# DMX_module.net
KiCad netlist of a schematic drawn in EAGLE
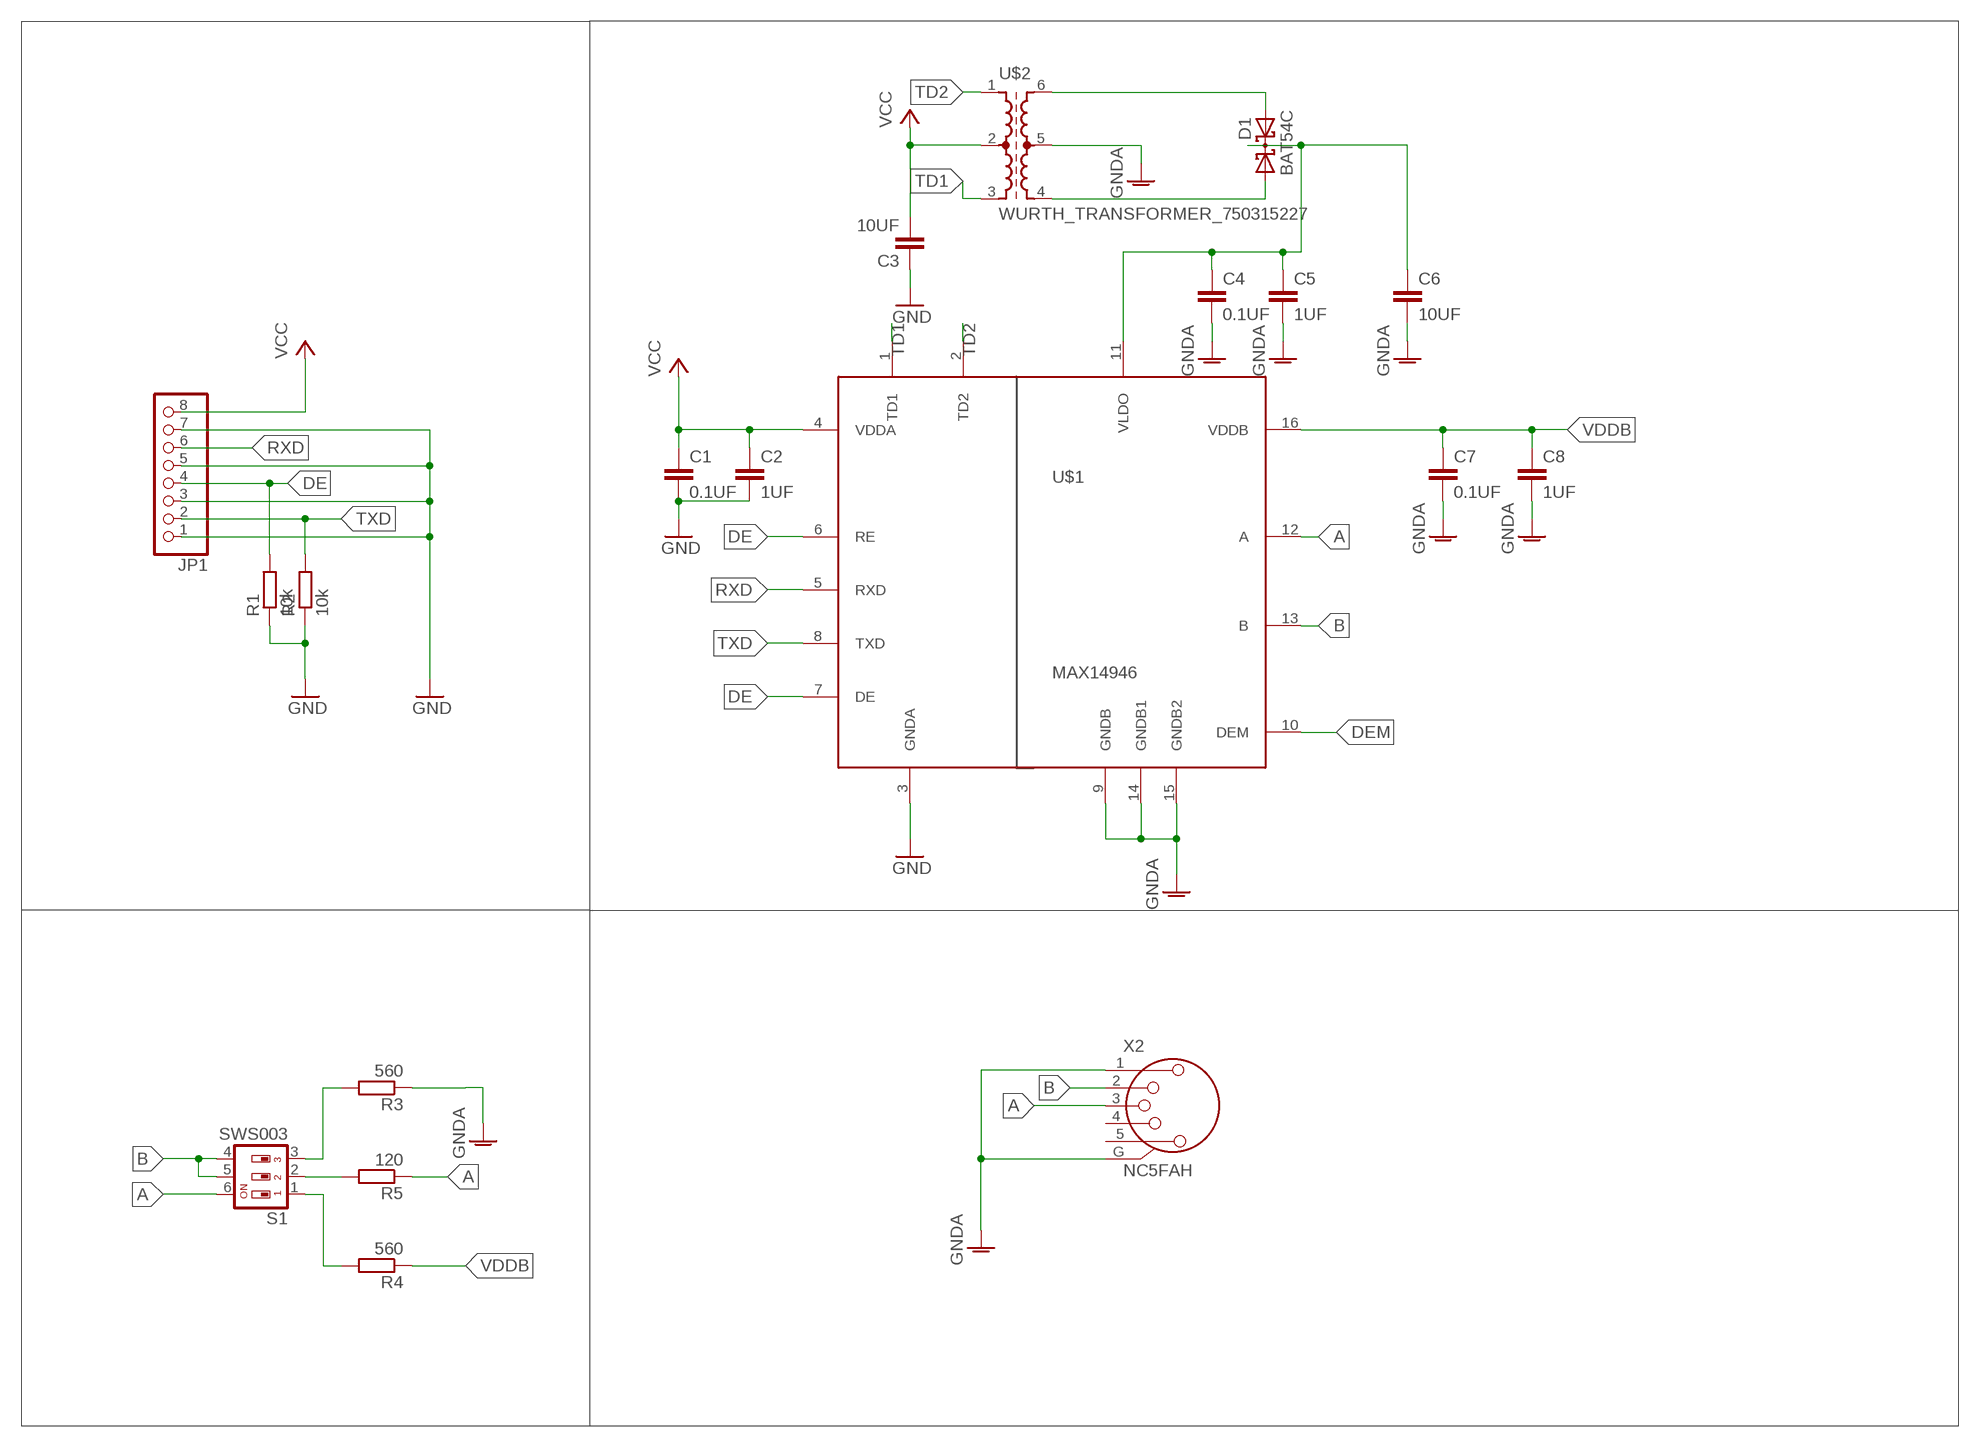
[diagram p0: schematic, sheet 1]

(export (version "E")
  (design (tool "Eeschema 10.0.6"))
  (components
    (comp (ref "C1")
      (value "0.1UF")
      (footprint "eagle-import:C0603")
      (fields (field (name "MF") "AVX") (field (name "MPN") "06033C104KAT2A"))
      (libsource (lib "eagle-import") (part "C-EUC0603"))
    )
    (comp (ref "C2")
      (value "1UF")
      (footprint "eagle-import:C0603")
      (fields (field (name "MF") "AVX") (field (name "MPN") "0603YC105KAT4A"))
      (libsource (lib "eagle-import") (part "C-EUC0603"))
    )
    (comp (ref "C3")
      (value "10UF")
      (footprint "eagle-import:C0805")
      (fields (field (name "MF") "AVX") (field (name "MPN") "08056G106ZAT2A"))
      (libsource (lib "eagle-import") (part "C-EUC0805"))
    )
    (comp (ref "C4")
      (value "0.1UF")
      (footprint "eagle-import:C0603")
      (fields (field (name "MF") "AVX") (field (name "MPN") "06033C104KAT2A"))
      (libsource (lib "eagle-import") (part "C-EUC0603"))
    )
    (comp (ref "C5")
      (value "1UF")
      (footprint "eagle-import:C0603")
      (fields (field (name "MF") "AVX") (field (name "MPN") "0603YC105KAT4A"))
      (libsource (lib "eagle-import") (part "C-EUC0603"))
    )
    (comp (ref "C6")
      (value "10UF")
      (footprint "eagle-import:C0805")
      (fields (field (name "MF") "AVX") (field (name "MPN") "08056G106ZAT2A"))
      (libsource (lib "eagle-import") (part "C-EUC0805"))
    )
    (comp (ref "C7")
      (value "0.1UF")
      (footprint "eagle-import:C0603")
      (fields (field (name "MF") "AVX") (field (name "MPN") "06033C104KAT2A"))
      (libsource (lib "eagle-import") (part "C-EUC0603"))
    )
    (comp (ref "C8")
      (value "1UF")
      (footprint "eagle-import:C0603")
      (fields (field (name "MF") "AVX") (field (name "MPN") "0603YC105KAT4A"))
      (libsource (lib "eagle-import") (part "C-EUC0603"))
    )
    (comp (ref "D1")
      (value "BAT54C")
      (footprint "eagle-import:SOT23")
      (fields (field (name "MF") "ROHM Semiconductor") (field (name "MPN") "755-BAT54AHMFHT116 "))
      (libsource (lib "eagle-import") (part "BAT54C"))
    )
    (comp (ref "JP1")
      (value "PINHD-1X8/90")
      (footprint "eagle-import:1X08_90")
      (fields (field (name "MF") "CONNFLY") (field (name "MPN") "DS1022-1*20RDF1-1"))
      (libsource (lib "eagle-import") (part "PINHD-1X8/90"))
    )
    (comp (ref "R1")
      (value "10k")
      (footprint "eagle-import:R0603")
      (fields (field (name "MF") "Yageo") (field (name "MPN") "RC0603JR-0710KA"))
      (libsource (lib "eagle-import") (part "R-EU_R0603"))
    )
    (comp (ref "R2")
      (value "10k")
      (footprint "eagle-import:R0603")
      (fields (field (name "MF") "Yageo") (field (name "MPN") "RC0603JR-0710KA"))
      (libsource (lib "eagle-import") (part "R-EU_R0603"))
    )
    (comp (ref "R3")
      (value "560")
      (footprint "eagle-import:R0603")
      (fields (field (name "MF") "Yageo") (field (name "MPN") "RC0603FR-13560RL"))
      (libsource (lib "eagle-import") (part "R-EU_R0603"))
    )
    (comp (ref "R4")
      (value "560")
      (footprint "eagle-import:R0603")
      (fields (field (name "MF") "Yageo") (field (name "MPN") "RC0603FR-13560RL"))
      (libsource (lib "eagle-import") (part "R-EU_R0603"))
    )
    (comp (ref "R5")
      (value "120")
      (footprint "eagle-import:R0603")
      (fields (field (name "MF") "Yageo") (field (name "MPN") "RC0603FR-10120RL"))
      (libsource (lib "eagle-import") (part "R-EU_R0603"))
    )
    (comp (ref "S1")
      (value "SWS003")
      (footprint "eagle-import:SMS-003")
      (fields (field (name "MF") "CTS Electronic Components") (field (name "MPN") "774-2193MST "))
      (libsource (lib "eagle-import") (part "SWS003"))
    )
    (comp (ref "U$1")
      (value "MAX14946")
      (footprint "eagle-import:SOIC16W")
      (fields (field (name "MF") "Maxim") (field (name "MPN") "700-MAX14946EWE+ "))
      (libsource (lib "eagle-import") (part "MAX14946"))
    )
    (comp (ref "U$2")
      (value "WURTH_TRANSFORMER_750315227")
      (footprint "eagle-import:WURTH750315227")
      (fields (field (name "MF") "Wurth Electronics") (field (name "MPN") "710-750315227 "))
      (libsource (lib "eagle-import") (part "WURTH_TRANSFORMER_750315227"))
    )
    (comp (ref "X2")
      (value "NC5FAH")
      (footprint "eagle-import:NC5FAH")
      (fields (field (name "MF") "FARNELL") (field (name "MF_1") "Neutrik"))
      (libsource (lib "eagle-import") (part "NC5FAH"))
    )
  )
  (nets
    (net (code "1") (name "A") (class "Default")
      (node (ref "R5") (pin "1") (pinfunction "1_1") (pintype "passive"))
      (node (ref "S1") (pin "6") (pinfunction "6_6") (pintype "passive"))
      (node (ref "U$1") (pin "12") (pinfunction "A_12") (pintype "bidirectional"))
      (node (ref "X2") (pin "3") (pinfunction "3_3") (pintype "passive"))
    )
    (net (code "2") (name "B") (class "Default")
      (node (ref "S1") (pin "4") (pinfunction "4_4") (pintype "passive"))
      (node (ref "S1") (pin "5") (pinfunction "5_5") (pintype "passive"))
      (node (ref "U$1") (pin "13") (pinfunction "B_13") (pintype "bidirectional"))
      (node (ref "X2") (pin "2") (pinfunction "2_2") (pintype "passive"))
    )
    (net (code "3") (name "DE") (class "Default")
      (node (ref "JP1") (pin "4") (pinfunction "4_4") (pintype "passive"))
      (node (ref "R1") (pin "2") (pinfunction "2_2") (pintype "passive"))
      (node (ref "U$1") (pin "6") (pinfunction "RE_6") (pintype "bidirectional"))
      (node (ref "U$1") (pin "7") (pinfunction "DE_7") (pintype "bidirectional"))
    )
    (net (code "4") (name "DEM") (class "Default")
      (node (ref "U$1") (pin "10") (pinfunction "DEM_10") (pintype "bidirectional"))
    )
    (net (code "5") (name "GND") (class "Default")
      (node (ref "C1") (pin "2") (pinfunction "2_2") (pintype "passive"))
      (node (ref "C2") (pin "2") (pinfunction "2_2") (pintype "passive"))
      (node (ref "C3") (pin "1") (pinfunction "1_1") (pintype "passive"))
      (node (ref "JP1") (pin "1") (pinfunction "1_1") (pintype "passive"))
      (node (ref "JP1") (pin "3") (pinfunction "3_3") (pintype "passive"))
      (node (ref "JP1") (pin "5") (pinfunction "5_5") (pintype "passive"))
      (node (ref "JP1") (pin "7") (pinfunction "7_7") (pintype "passive"))
      (node (ref "R1") (pin "1") (pinfunction "1_1") (pintype "passive"))
      (node (ref "R2") (pin "1") (pinfunction "1_1") (pintype "passive"))
      (node (ref "U$1") (pin "3") (pinfunction "GNDA_3") (pintype "bidirectional"))
    )
    (net (code "6") (name "GNDA") (class "Default")
      (node (ref "C4") (pin "2") (pinfunction "2_2") (pintype "passive"))
      (node (ref "C5") (pin "2") (pinfunction "2_2") (pintype "passive"))
      (node (ref "C6") (pin "2") (pinfunction "2_2") (pintype "passive"))
      (node (ref "C7") (pin "2") (pinfunction "2_2") (pintype "passive"))
      (node (ref "C8") (pin "2") (pinfunction "2_2") (pintype "passive"))
      (node (ref "R3") (pin "1") (pinfunction "1_1") (pintype "passive"))
      (node (ref "U$1") (pin "14") (pinfunction "GNDB1_14") (pintype "bidirectional"))
      (node (ref "U$1") (pin "15") (pinfunction "GNDB2_15") (pintype "bidirectional"))
      (node (ref "U$1") (pin "9") (pinfunction "GNDB_9") (pintype "bidirectional"))
      (node (ref "U$2") (pin "5") (pinfunction "5_5") (pintype "passive"))
      (node (ref "X2") (pin "1") (pinfunction "1_1") (pintype "passive"))
      (node (ref "X2") (pin "G") (pinfunction "G_G") (pintype "passive"))
    )
    (net (code "7") (name "Net-(D1-A1)") (class "Default")
      (node (ref "D1") (pin "1") (pinfunction "A1_1") (pintype "passive"))
      (node (ref "U$2") (pin "4") (pinfunction "4_4") (pintype "passive"))
    )
    (net (code "8") (name "Net-(D1-A2)") (class "Default")
      (node (ref "D1") (pin "2") (pinfunction "A2_2") (pintype "passive"))
      (node (ref "U$2") (pin "6") (pinfunction "6_6") (pintype "passive"))
    )
    (net (code "9") (name "Net-(D1-CC)") (class "Default")
      (node (ref "C4") (pin "1") (pinfunction "1_1") (pintype "passive"))
      (node (ref "C5") (pin "1") (pinfunction "1_1") (pintype "passive"))
      (node (ref "C6") (pin "1") (pinfunction "1_1") (pintype "passive"))
      (node (ref "D1") (pin "3") (pinfunction "CC_3") (pintype "passive"))
      (node (ref "U$1") (pin "11") (pinfunction "VLDO_11") (pintype "bidirectional"))
    )
    (net (code "10") (name "Net-(R3-Pad2)") (class "Default")
      (node (ref "R3") (pin "2") (pinfunction "2_2") (pintype "passive"))
      (node (ref "S1") (pin "3") (pinfunction "3_3") (pintype "passive"))
    )
    (net (code "11") (name "Net-(R4-Pad2)") (class "Default")
      (node (ref "R4") (pin "2") (pinfunction "2_2") (pintype "passive"))
      (node (ref "S1") (pin "1") (pinfunction "1_1") (pintype "passive"))
    )
    (net (code "12") (name "Net-(R5-Pad2)") (class "Default")
      (node (ref "R5") (pin "2") (pinfunction "2_2") (pintype "passive"))
      (node (ref "S1") (pin "2") (pinfunction "2_2") (pintype "passive"))
    )
    (net (code "13") (name "RXD") (class "Default")
      (node (ref "JP1") (pin "6") (pinfunction "6_6") (pintype "passive"))
      (node (ref "U$1") (pin "5") (pinfunction "RXD_5") (pintype "bidirectional"))
    )
    (net (code "14") (name "TD1") (class "Default")
      (node (ref "U$1") (pin "1") (pinfunction "TD1_1") (pintype "bidirectional"))
      (node (ref "U$2") (pin "3") (pinfunction "3_3") (pintype "passive"))
    )
    (net (code "15") (name "TD2") (class "Default")
      (node (ref "U$1") (pin "2") (pinfunction "TD2_2") (pintype "bidirectional"))
      (node (ref "U$2") (pin "1") (pinfunction "1_1") (pintype "passive"))
    )
    (net (code "16") (name "TXD") (class "Default")
      (node (ref "JP1") (pin "2") (pinfunction "2_2") (pintype "passive"))
      (node (ref "R2") (pin "2") (pinfunction "2_2") (pintype "passive"))
      (node (ref "U$1") (pin "8") (pinfunction "TXD_8") (pintype "bidirectional"))
    )
    (net (code "17") (name "VCC") (class "Default")
      (node (ref "C1") (pin "1") (pinfunction "1_1") (pintype "passive"))
      (node (ref "C2") (pin "1") (pinfunction "1_1") (pintype "passive"))
      (node (ref "C3") (pin "2") (pinfunction "2_2") (pintype "passive"))
      (node (ref "JP1") (pin "8") (pinfunction "8_8") (pintype "passive"))
      (node (ref "U$1") (pin "4") (pinfunction "VDDA_4") (pintype "bidirectional"))
      (node (ref "U$2") (pin "2") (pinfunction "2_2") (pintype "passive"))
    )
    (net (code "18") (name "VDDB") (class "Default")
      (node (ref "C7") (pin "1") (pinfunction "1_1") (pintype "passive"))
      (node (ref "C8") (pin "1") (pinfunction "1_1") (pintype "passive"))
      (node (ref "R4") (pin "1") (pinfunction "1_1") (pintype "passive"))
      (node (ref "U$1") (pin "16") (pinfunction "VDDB_16") (pintype "bidirectional"))
    )
    (net (code "19") (name "unconnected-(X2-Pad4)") (class "Default")
      (node (ref "X2") (pin "4") (pinfunction "4_4") (pintype "passive"))
    )
    (net (code "20") (name "unconnected-(X2-Pad5)") (class "Default")
      (node (ref "X2") (pin "5") (pinfunction "5_5") (pintype "passive"))
    )
  )
)
